# Controller_Sheet.net
KiCad netlist of a schematic drawn in Altium Designer
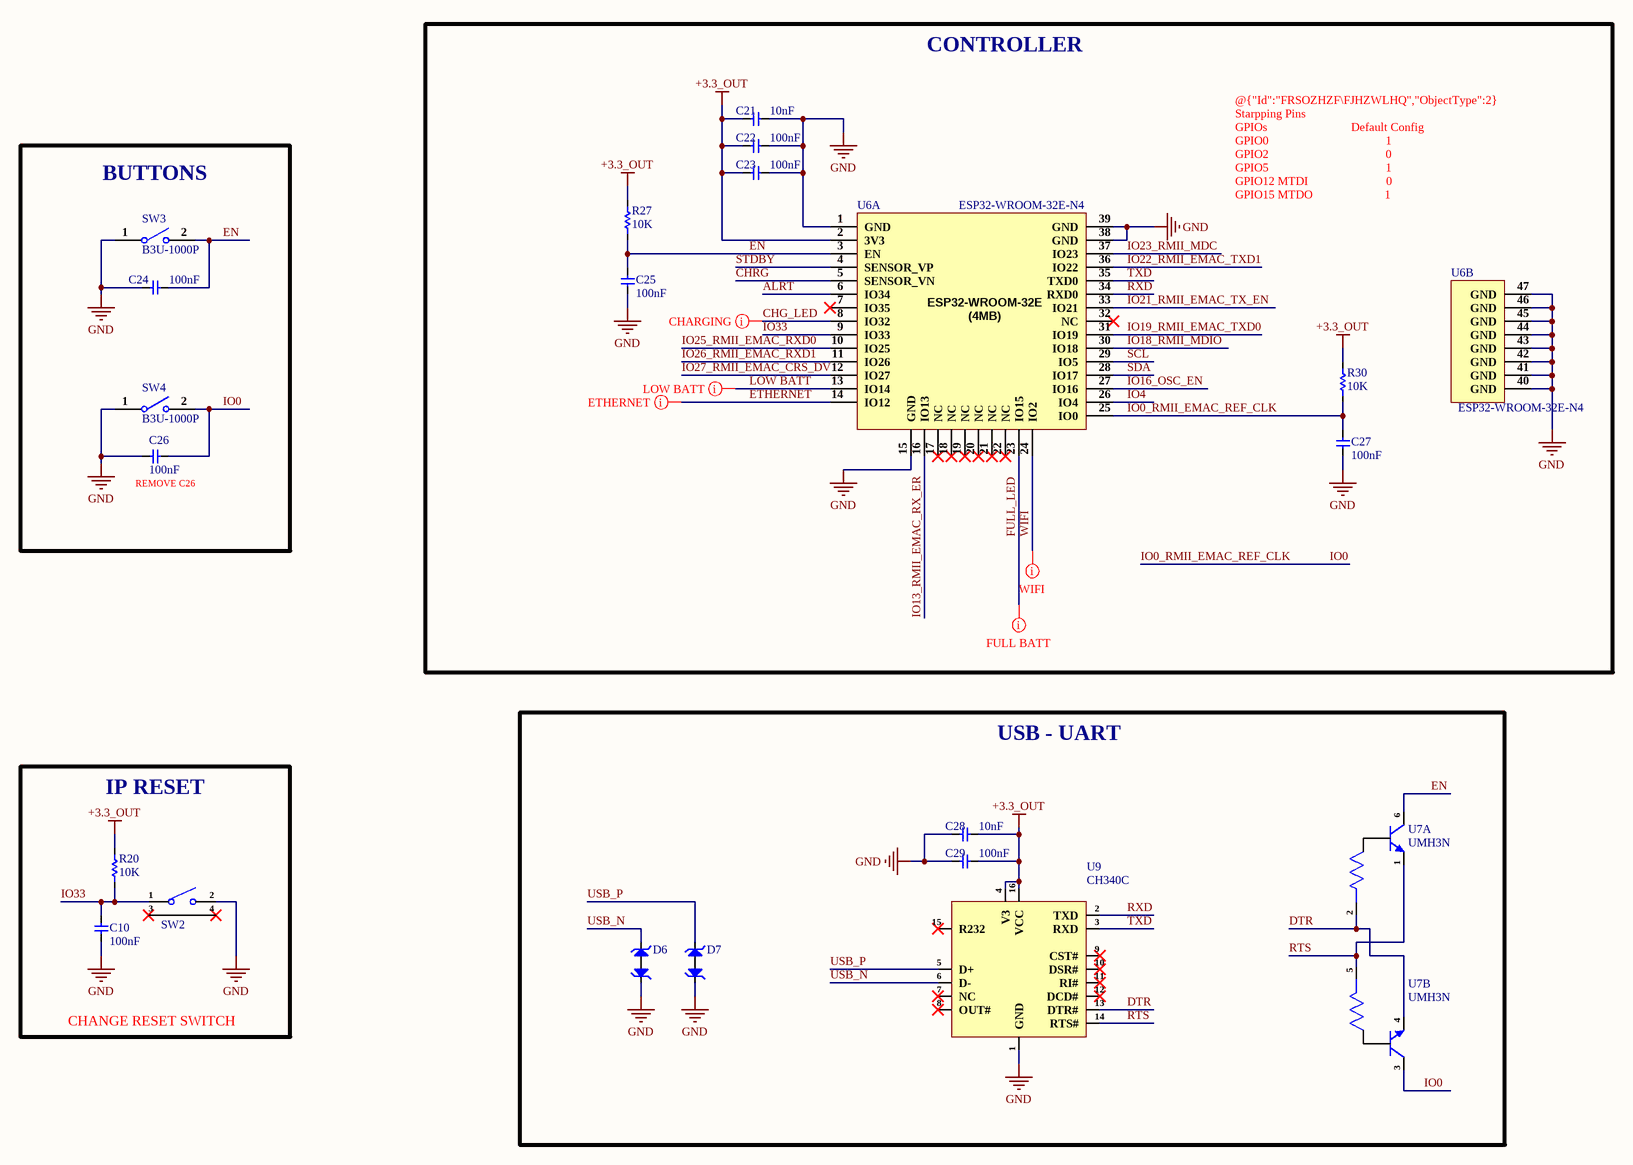
[diagram p0: Controller_Sheet.SchDoc]

(export (version "E")
  (design (tool "Eeschema 10.0.6"))
  (components
    (comp (ref "C10")
      (value "100nF")
      (footprint "cap-0402")
      (description "CAP CER 0.1UF 50V X7R 0402")
      (fields
        (field (name "MANUFACTURER") "TDK")
        (field (name "MANUFACTURER PART NUMBER") "C1005X7R1H104KT000F")
      )
      (libsource (lib "eSpark Libraries") (part "C1005X7R1H104KT000F"))
    )
    (comp (ref "C21")
      (value "10nF")
      (footprint "Cap-0402")
      (description "CAP CER 10000PF 25V X7R 0402")
      (fields
        (field (name "MANUFACTURER") "Yageo")
        (field (name "MANUFACTURER PART NUMBER") "CC0402KRX7R8BB103")
      )
      (libsource (lib "eSpark Libraries") (part "CC0402KRX7R8BB103"))
    )
    (comp (ref "C22")
      (value "100nF")
      (footprint "cap-0402")
      (description "CAP CER 0.1UF 50V X7R 0402")
      (fields
        (field (name "MANUFACTURER") "TDK")
        (field (name "MANUFACTURER PART NUMBER") "C1005X7R1H104KT000F")
      )
      (libsource (lib "eSpark Libraries") (part "C1005X7R1H104KT000F"))
    )
    (comp (ref "C23")
      (value "100nF")
      (footprint "cap-0402")
      (description "CAP CER 0.1UF 50V X7R 0402")
      (fields
        (field (name "MANUFACTURER") "TDK")
        (field (name "MANUFACTURER PART NUMBER") "C1005X7R1H104KT000F")
      )
      (libsource (lib "eSpark Libraries") (part "C1005X7R1H104KT000F"))
    )
    (comp (ref "C24")
      (value "100nF")
      (footprint "cap-0402")
      (description "CAP CER 0.1UF 50V X7R 0402")
      (fields
        (field (name "MANUFACTURER") "TDK")
        (field (name "MANUFACTURER PART NUMBER") "C1005X7R1H104KT000F")
      )
      (libsource (lib "eSpark Libraries") (part "C1005X7R1H104KT000F"))
    )
    (comp (ref "C25")
      (value "100nF")
      (footprint "cap-0402")
      (description "CAP CER 0.1UF 50V X7R 0402")
      (fields
        (field (name "MANUFACTURER") "TDK")
        (field (name "MANUFACTURER PART NUMBER") "C1005X7R1H104KT000F")
      )
      (libsource (lib "eSpark Libraries") (part "C1005X7R1H104KT000F"))
    )
    (comp (ref "C26")
      (value "100nF")
      (footprint "cap-0402")
      (description "CAP CER 0.1UF 50V X7R 0402")
      (fields
        (field (name "MANUFACTURER") "TDK")
        (field (name "MANUFACTURER PART NUMBER") "C1005X7R1H104KT000F")
      )
      (libsource (lib "eSpark Libraries") (part "C1005X7R1H104KT000F"))
    )
    (comp (ref "C27")
      (value "100nF")
      (footprint "cap-0402")
      (description "CAP CER 0.1UF 50V X7R 0402")
      (fields
        (field (name "MANUFACTURER") "TDK")
        (field (name "MANUFACTURER PART NUMBER") "C1005X7R1H104KT000F")
      )
      (libsource (lib "eSpark Libraries") (part "C1005X7R1H104KT000F"))
    )
    (comp (ref "C28")
      (value "10nF")
      (footprint "Cap-0402")
      (description "CAP CER 10000PF 25V X7R 0402")
      (fields
        (field (name "MANUFACTURER") "Yageo")
        (field (name "MANUFACTURER PART NUMBER") "CC0402KRX7R8BB103")
      )
      (libsource (lib "eSpark Libraries") (part "CC0402KRX7R8BB103"))
    )
    (comp (ref "C29")
      (value "100nF")
      (footprint "cap-0402")
      (description "CAP CER 0.1UF 50V X7R 0402")
      (fields
        (field (name "MANUFACTURER") "TDK")
        (field (name "MANUFACTURER PART NUMBER") "C1005X7R1H104KT000F")
      )
      (libsource (lib "eSpark Libraries") (part "C1005X7R1H104KT000F"))
    )
    (comp (ref "D6")
      (value "PESD5V0H1BSFYL")
      (footprint "DSN0603-2")
      (description "TVS DIODE 5VWM 6.3VC DSN0603-2")
      (fields (field (name "MANUFACTURER") "Nexperia") (field (name "LCSC PART NUMBER") "C477989"))
      (libsource (lib "eSpark Libraries") (part "PESD5V0H1BSFYL"))
    )
    (comp (ref "D7")
      (value "PESD5V0H1BSFYL")
      (footprint "DSN0603-2")
      (description "TVS DIODE 5VWM 6.3VC DSN0603-2")
      (fields (field (name "MANUFACTURER") "Nexperia") (field (name "LCSC PART NUMBER") "C477989"))
      (libsource (lib "eSpark Libraries") (part "PESD5V0H1BSFYL"))
    )
    (comp (ref "R20")
      (value "10K")
      (footprint "Res-0402")
      (description "RES 10K OHM 1% 1/16W 0402")
      (fields
        (field (name "MANUFACTURER") "Yageo")
        (field (name "MANUFACTURER PART NUMBER") "RC0402FR-0710KL")
      )
      (libsource (lib "eSpark Libraries") (part "RC0402FR-0710KL"))
    )
    (comp (ref "R27")
      (value "10K")
      (footprint "Res-0402")
      (description "RES 10K OHM 1% 1/16W 0402")
      (fields
        (field (name "MANUFACTURER") "Yageo")
        (field (name "MANUFACTURER PART NUMBER") "RC0402FR-0710KL")
      )
      (libsource (lib "eSpark Libraries") (part "RC0402FR-0710KL"))
    )
    (comp (ref "R30")
      (value "10K")
      (footprint "Res-0402")
      (description "RES 10K OHM 1% 1/16W 0402")
      (fields
        (field (name "MANUFACTURER") "Yageo")
        (field (name "MANUFACTURER PART NUMBER") "RC0402FR-0710KL")
      )
      (libsource (lib "eSpark Libraries") (part "RC0402FR-0710KL"))
    )
    (comp (ref "SW2")
      (value "1-1825027-4")
      (footprint "1-1825027-4")
      (fields (field (name "MANUFACTURER") "TE Connectivity") (field (name "LCSC PART NUMBER") "C2928195"))
      (libsource (lib "eSpark Libraries") (part "1-1825027-4"))
    )
    (comp (ref "SW3")
      (value "B3U-1000P")
      (footprint "B3U-1000P")
      (description "SWITCH TACTILE SPST-NO 0.05A 12V")
      (fields (field (name "MANUFACTURER") "Omron") (field (name "LCSC PART NUMBER") "C231329"))
      (libsource (lib "eSpark Libraries") (part "B3U-1000P"))
    )
    (comp (ref "SW4")
      (value "B3U-1000P")
      (footprint "B3U-1000P")
      (description "SWITCH TACTILE SPST-NO 0.05A 12V")
      (fields (field (name "MANUFACTURER") "Omron") (field (name "LCSC PART NUMBER") "C231329"))
      (libsource (lib "eSpark Libraries") (part "B3U-1000P"))
    )
    (comp (ref "U6")
      (value "ESP32-WROOM-32E-N4")
      (footprint "38-SMD Module")
      (description "RX TXRX MOD WIFI TRACE ANT SMD")
      (fields (field (name "MANUFACTURER") "Espressif Systems") (field (name "LCSC PART NUMBER") "C701341"))
      (libsource (lib "eSpark Libraries") (part "ESP32-WROOM-32E-N4"))
    )
    (comp (ref "U7")
      (value "UMH3N")
      (footprint "SC-70-6_")
      (description "2 NPN pre-biased (Dual) 150mW 100mA 50V SC-70-6(SOT-363) Digital Transistors ROHS")
      (fields (field (name "MANUFACTURER") "Changjiang") (field (name "LCSC PART NUMBER") "C62892"))
      (libsource (lib "eSpark Libraries") (part "UMH3N"))
    )
    (comp (ref "U9")
      (value "CH340C")
      (footprint "SOP-16")
      (description "2Mbps Transceiver USB 2.0 SOP-16 USB ICs ROHS")
      (fields (field (name "MANUFACTURER") "WCH") (field (name "LCSC PART NUMBER") "C84681"))
      (libsource (lib "eSpark Libraries") (part "CH340C"))
    )
  )
  (nets
    (net (code "1") (name "+3.3_OUT") (class "Default")
      (node (ref "C21") (pin "2") (pinfunction "2_2") (pintype "passive"))
      (node (ref "C22") (pin "2") (pinfunction "2_2") (pintype "passive"))
      (node (ref "C23") (pin "2") (pinfunction "2_2") (pintype "passive"))
      (node (ref "C28") (pin "1") (pinfunction "1_1") (pintype "passive"))
      (node (ref "C29") (pin "1") (pinfunction "1_1") (pintype "passive"))
      (node (ref "R20") (pin "2") (pinfunction "2_2") (pintype "passive"))
      (node (ref "R27") (pin "2") (pinfunction "2_2") (pintype "passive"))
      (node (ref "R30") (pin "2") (pinfunction "2_2") (pintype "passive"))
      (node (ref "U6") (pin "2") (pinfunction "3V3_2") (pintype "passive"))
      (node (ref "U9") (pin "16") (pinfunction "VCC_16") (pintype "passive"))
      (node (ref "U9") (pin "4") (pinfunction "V3_4") (pintype "passive"))
    )
    (net (code "2") (name "/ALRT") (class "Default")
      (node (ref "U6") (pin "6") (pinfunction "IO34_6") (pintype "passive"))
    )
    (net (code "3") (name "/CHG_LED") (class "Default")
      (node (ref "U6") (pin "8") (pinfunction "IO32_8") (pintype "passive"))
    )
    (net (code "4") (name "/CHRG") (class "Default")
      (node (ref "U6") (pin "5") (pinfunction "SENSOR_VN_5") (pintype "passive"))
    )
    (net (code "5") (name "/DTR") (class "Default")
      (node (ref "U7") (pin "2") (pintype "passive"))
      (node (ref "U7") (pin "4") (pinfunction "E_4") (pintype "passive"))
      (node (ref "U9") (pin "13") (pinfunction "DTR#_13") (pintype "passive"))
    )
    (net (code "6") (name "/EN") (class "Default")
      (node (ref "C24") (pin "1") (pinfunction "1_1") (pintype "passive"))
      (node (ref "C25") (pin "2") (pinfunction "2_2") (pintype "passive"))
      (node (ref "R27") (pin "1") (pinfunction "1_1") (pintype "passive"))
      (node (ref "SW3") (pin "2") (pinfunction "2_2") (pintype "passive"))
      (node (ref "U6") (pin "3") (pinfunction "EN_3") (pintype "passive"))
      (node (ref "U7") (pin "6") (pinfunction "C_6") (pintype "passive"))
    )
    (net (code "7") (name "/ETHERNET") (class "Default")
      (node (ref "U6") (pin "14") (pinfunction "IO12_14") (pintype "passive"))
    )
    (net (code "8") (name "/FULL_LED") (class "Default")
      (node (ref "U6") (pin "23") (pinfunction "IO15_23") (pintype "passive"))
    )
    (net (code "9") (name "/IO0") (class "Default")
      (node (ref "C26") (pin "1") (pinfunction "1_1") (pintype "passive"))
      (node (ref "C27") (pin "2") (pinfunction "2_2") (pintype "passive"))
      (node (ref "R30") (pin "1") (pinfunction "1_1") (pintype "passive"))
      (node (ref "SW4") (pin "2") (pinfunction "2_2") (pintype "passive"))
      (node (ref "U6") (pin "25") (pinfunction "IO0_25") (pintype "passive"))
      (node (ref "U7") (pin "3") (pinfunction "C_3") (pintype "passive"))
    )
    (net (code "10") (name "/IO4") (class "Default")
      (node (ref "U6") (pin "26") (pinfunction "IO4_26") (pintype "passive"))
    )
    (net (code "11") (name "/IO13_RMII_EMAC_RX_ER") (class "Default")
      (node (ref "U6") (pin "16") (pinfunction "IO13_16") (pintype "passive"))
    )
    (net (code "12") (name "/IO16_OSC_EN") (class "Default")
      (node (ref "U6") (pin "27") (pinfunction "IO16_27") (pintype "passive"))
    )
    (net (code "13") (name "/IO18_RMII_MDIO") (class "Default")
      (node (ref "U6") (pin "30") (pinfunction "IO18_30") (pintype "passive"))
    )
    (net (code "14") (name "/IO19_RMII_EMAC_TXD0") (class "Default")
      (node (ref "U6") (pin "31") (pinfunction "IO19_31") (pintype "passive"))
    )
    (net (code "15") (name "/IO21_RMII_EMAC_TX_EN") (class "Default")
      (node (ref "U6") (pin "33") (pinfunction "IO21_33") (pintype "passive"))
    )
    (net (code "16") (name "/IO22_RMII_EMAC_TXD1") (class "Default")
      (node (ref "U6") (pin "36") (pinfunction "IO22_36") (pintype "passive"))
    )
    (net (code "17") (name "/IO23_RMII_MDC") (class "Default")
      (node (ref "U6") (pin "37") (pinfunction "IO23_37") (pintype "passive"))
    )
    (net (code "18") (name "/IO25_RMII_EMAC_RXD0") (class "Default")
      (node (ref "U6") (pin "10") (pinfunction "IO25_10") (pintype "passive"))
    )
    (net (code "19") (name "/IO26_RMII_EMAC_RXD1") (class "Default")
      (node (ref "U6") (pin "11") (pinfunction "IO26_11") (pintype "passive"))
    )
    (net (code "20") (name "/IO27_RMII_EMAC_CRS_DV") (class "Default")
      (node (ref "U6") (pin "12") (pinfunction "IO27_12") (pintype "passive"))
    )
    (net (code "21") (name "/IO33") (class "Default")
      (node (ref "C10") (pin "1") (pinfunction "1_1") (pintype "passive"))
      (node (ref "R20") (pin "1") (pinfunction "1_1") (pintype "passive"))
      (node (ref "SW2") (pin "1") (pinfunction "2_1") (pintype "passive"))
      (node (ref "U6") (pin "9") (pinfunction "IO33_9") (pintype "passive"))
    )
    (net (code "22") (name "/LOW BATT") (class "Default")
      (node (ref "U6") (pin "13") (pinfunction "IO14_13") (pintype "passive"))
    )
    (net (code "23") (name "/RTS") (class "Default")
      (node (ref "U7") (pin "1") (pinfunction "E_1") (pintype "passive"))
      (node (ref "U7") (pin "5") (pintype "passive"))
      (node (ref "U9") (pin "14") (pinfunction "RTS#_14") (pintype "passive"))
    )
    (net (code "24") (name "/RXD") (class "Default")
      (node (ref "U6") (pin "34") (pinfunction "RXD0_34") (pintype "passive"))
      (node (ref "U9") (pin "2") (pinfunction "TXD_2") (pintype "passive"))
    )
    (net (code "25") (name "/SCL") (class "Default")
      (node (ref "U6") (pin "29") (pinfunction "IO5_29") (pintype "passive"))
    )
    (net (code "26") (name "/SDA") (class "Default")
      (node (ref "U6") (pin "28") (pinfunction "IO17_28") (pintype "passive"))
    )
    (net (code "27") (name "/STDBY") (class "Default")
      (node (ref "U6") (pin "4") (pinfunction "SENSOR_VP_4") (pintype "passive"))
    )
    (net (code "28") (name "/TXD") (class "Default")
      (node (ref "U6") (pin "35") (pinfunction "TXD0_35") (pintype "passive"))
      (node (ref "U9") (pin "3") (pinfunction "RXD_3") (pintype "passive"))
    )
    (net (code "29") (name "/USB_N") (class "Default")
      (node (ref "D6") (pin "2") (pinfunction "2_2") (pintype "passive"))
      (node (ref "U9") (pin "6") (pinfunction "D-_6") (pintype "passive"))
    )
    (net (code "30") (name "/USB_P") (class "Default")
      (node (ref "D7") (pin "2") (pinfunction "2_2") (pintype "passive"))
      (node (ref "U9") (pin "5") (pinfunction "D+_5") (pintype "passive"))
    )
    (net (code "31") (name "/WIFI") (class "Default")
      (node (ref "U6") (pin "24") (pinfunction "IO2_24") (pintype "passive"))
    )
    (net (code "32") (name "GND") (class "Default")
      (node (ref "C10") (pin "2") (pinfunction "2_2") (pintype "passive"))
      (node (ref "C21") (pin "1") (pinfunction "1_1") (pintype "passive"))
      (node (ref "C22") (pin "1") (pinfunction "1_1") (pintype "passive"))
      (node (ref "C23") (pin "1") (pinfunction "1_1") (pintype "passive"))
      (node (ref "C24") (pin "2") (pinfunction "2_2") (pintype "passive"))
      (node (ref "C25") (pin "1") (pinfunction "1_1") (pintype "passive"))
      (node (ref "C26") (pin "2") (pinfunction "2_2") (pintype "passive"))
      (node (ref "C27") (pin "1") (pinfunction "1_1") (pintype "passive"))
      (node (ref "C28") (pin "2") (pinfunction "2_2") (pintype "passive"))
      (node (ref "C29") (pin "2") (pinfunction "2_2") (pintype "passive"))
      (node (ref "D6") (pin "1") (pinfunction "1_1") (pintype "passive"))
      (node (ref "D7") (pin "1") (pinfunction "1_1") (pintype "passive"))
      (node (ref "SW2") (pin "2") (pinfunction "2_2") (pintype "passive"))
      (node (ref "SW3") (pin "1") (pinfunction "1_1") (pintype "passive"))
      (node (ref "SW4") (pin "1") (pinfunction "1_1") (pintype "passive"))
      (node (ref "U6") (pin "1") (pinfunction "GND_1") (pintype "passive"))
      (node (ref "U6") (pin "15") (pinfunction "GND_15") (pintype "passive"))
      (node (ref "U6") (pin "38") (pinfunction "GND_38") (pintype "passive"))
      (node (ref "U6") (pin "39") (pinfunction "GND_39") (pintype "passive"))
      (node (ref "U6") (pin "40") (pinfunction "GND_40") (pintype "passive"))
      (node (ref "U6") (pin "41") (pinfunction "GND_41") (pintype "passive"))
      (node (ref "U6") (pin "42") (pinfunction "GND_42") (pintype "passive"))
      (node (ref "U6") (pin "43") (pinfunction "GND_43") (pintype "passive"))
      (node (ref "U6") (pin "44") (pinfunction "GND_44") (pintype "passive"))
      (node (ref "U6") (pin "45") (pinfunction "GND_45") (pintype "passive"))
      (node (ref "U6") (pin "46") (pinfunction "GND_46") (pintype "passive"))
      (node (ref "U6") (pin "47") (pinfunction "GND_47") (pintype "passive"))
      (node (ref "U9") (pin "1") (pinfunction "GND_1") (pintype "passive"))
    )
    (net (code "33") (name "unconnected-(SW2-Pad3)") (class "Default")
      (node (ref "SW2") (pin "3") (pinfunction "3_3") (pintype "passive+no_connect"))
    )
    (net (code "34") (name "unconnected-(SW2-Pad4)") (class "Default")
      (node (ref "SW2") (pin "4") (pinfunction "4_4") (pintype "passive+no_connect"))
    )
    (net (code "35") (name "unconnected-(U6A-IO35-Pad7)") (class "Default")
      (node (ref "U6") (pin "7") (pinfunction "IO35_7") (pintype "passive+no_connect"))
    )
    (net (code "36") (name "unconnected-(U6A-NC-Pad17)") (class "Default")
      (node (ref "U6") (pin "17") (pinfunction "NC_17") (pintype "passive+no_connect"))
    )
    (net (code "37") (name "unconnected-(U6A-NC-Pad18)") (class "Default")
      (node (ref "U6") (pin "18") (pinfunction "NC_18") (pintype "passive+no_connect"))
    )
    (net (code "38") (name "unconnected-(U6A-NC-Pad19)") (class "Default")
      (node (ref "U6") (pin "19") (pinfunction "NC_19") (pintype "passive+no_connect"))
    )
    (net (code "39") (name "unconnected-(U6A-NC-Pad20)") (class "Default")
      (node (ref "U6") (pin "20") (pinfunction "NC_20") (pintype "passive+no_connect"))
    )
    (net (code "40") (name "unconnected-(U6A-NC-Pad21)") (class "Default")
      (node (ref "U6") (pin "21") (pinfunction "NC_21") (pintype "passive+no_connect"))
    )
    (net (code "41") (name "unconnected-(U6A-NC-Pad22)") (class "Default")
      (node (ref "U6") (pin "22") (pinfunction "NC_22") (pintype "passive+no_connect"))
    )
    (net (code "42") (name "unconnected-(U6A-NC-Pad32)") (class "Default")
      (node (ref "U6") (pin "32") (pinfunction "NC_32") (pintype "passive+no_connect"))
    )
    (net (code "43") (name "unconnected-(U9-CST#-Pad9)") (class "Default")
      (node (ref "U9") (pin "9") (pinfunction "CST#_9") (pintype "passive+no_connect"))
    )
    (net (code "44") (name "unconnected-(U9-DCD#-Pad12)") (class "Default")
      (node (ref "U9") (pin "12") (pinfunction "DCD#_12") (pintype "passive+no_connect"))
    )
    (net (code "45") (name "unconnected-(U9-DSR#-Pad10)") (class "Default")
      (node (ref "U9") (pin "10") (pinfunction "DSR#_10") (pintype "passive+no_connect"))
    )
    (net (code "46") (name "unconnected-(U9-NC-Pad7)") (class "Default")
      (node (ref "U9") (pin "7") (pinfunction "NC_7") (pintype "passive+no_connect"))
    )
    (net (code "47") (name "unconnected-(U9-OUT#-Pad8)") (class "Default")
      (node (ref "U9") (pin "8") (pinfunction "OUT#_8") (pintype "passive+no_connect"))
    )
    (net (code "48") (name "unconnected-(U9-R232-Pad15)") (class "Default")
      (node (ref "U9") (pin "15") (pinfunction "R232_15") (pintype "passive+no_connect"))
    )
    (net (code "49") (name "unconnected-(U9-RI#-Pad11)") (class "Default")
      (node (ref "U9") (pin "11") (pinfunction "RI#_11") (pintype "passive+no_connect"))
    )
  )
)
